# STM32MP25XXAK_Power.net
KiCad netlist of a schematic drawn in Altium Designer
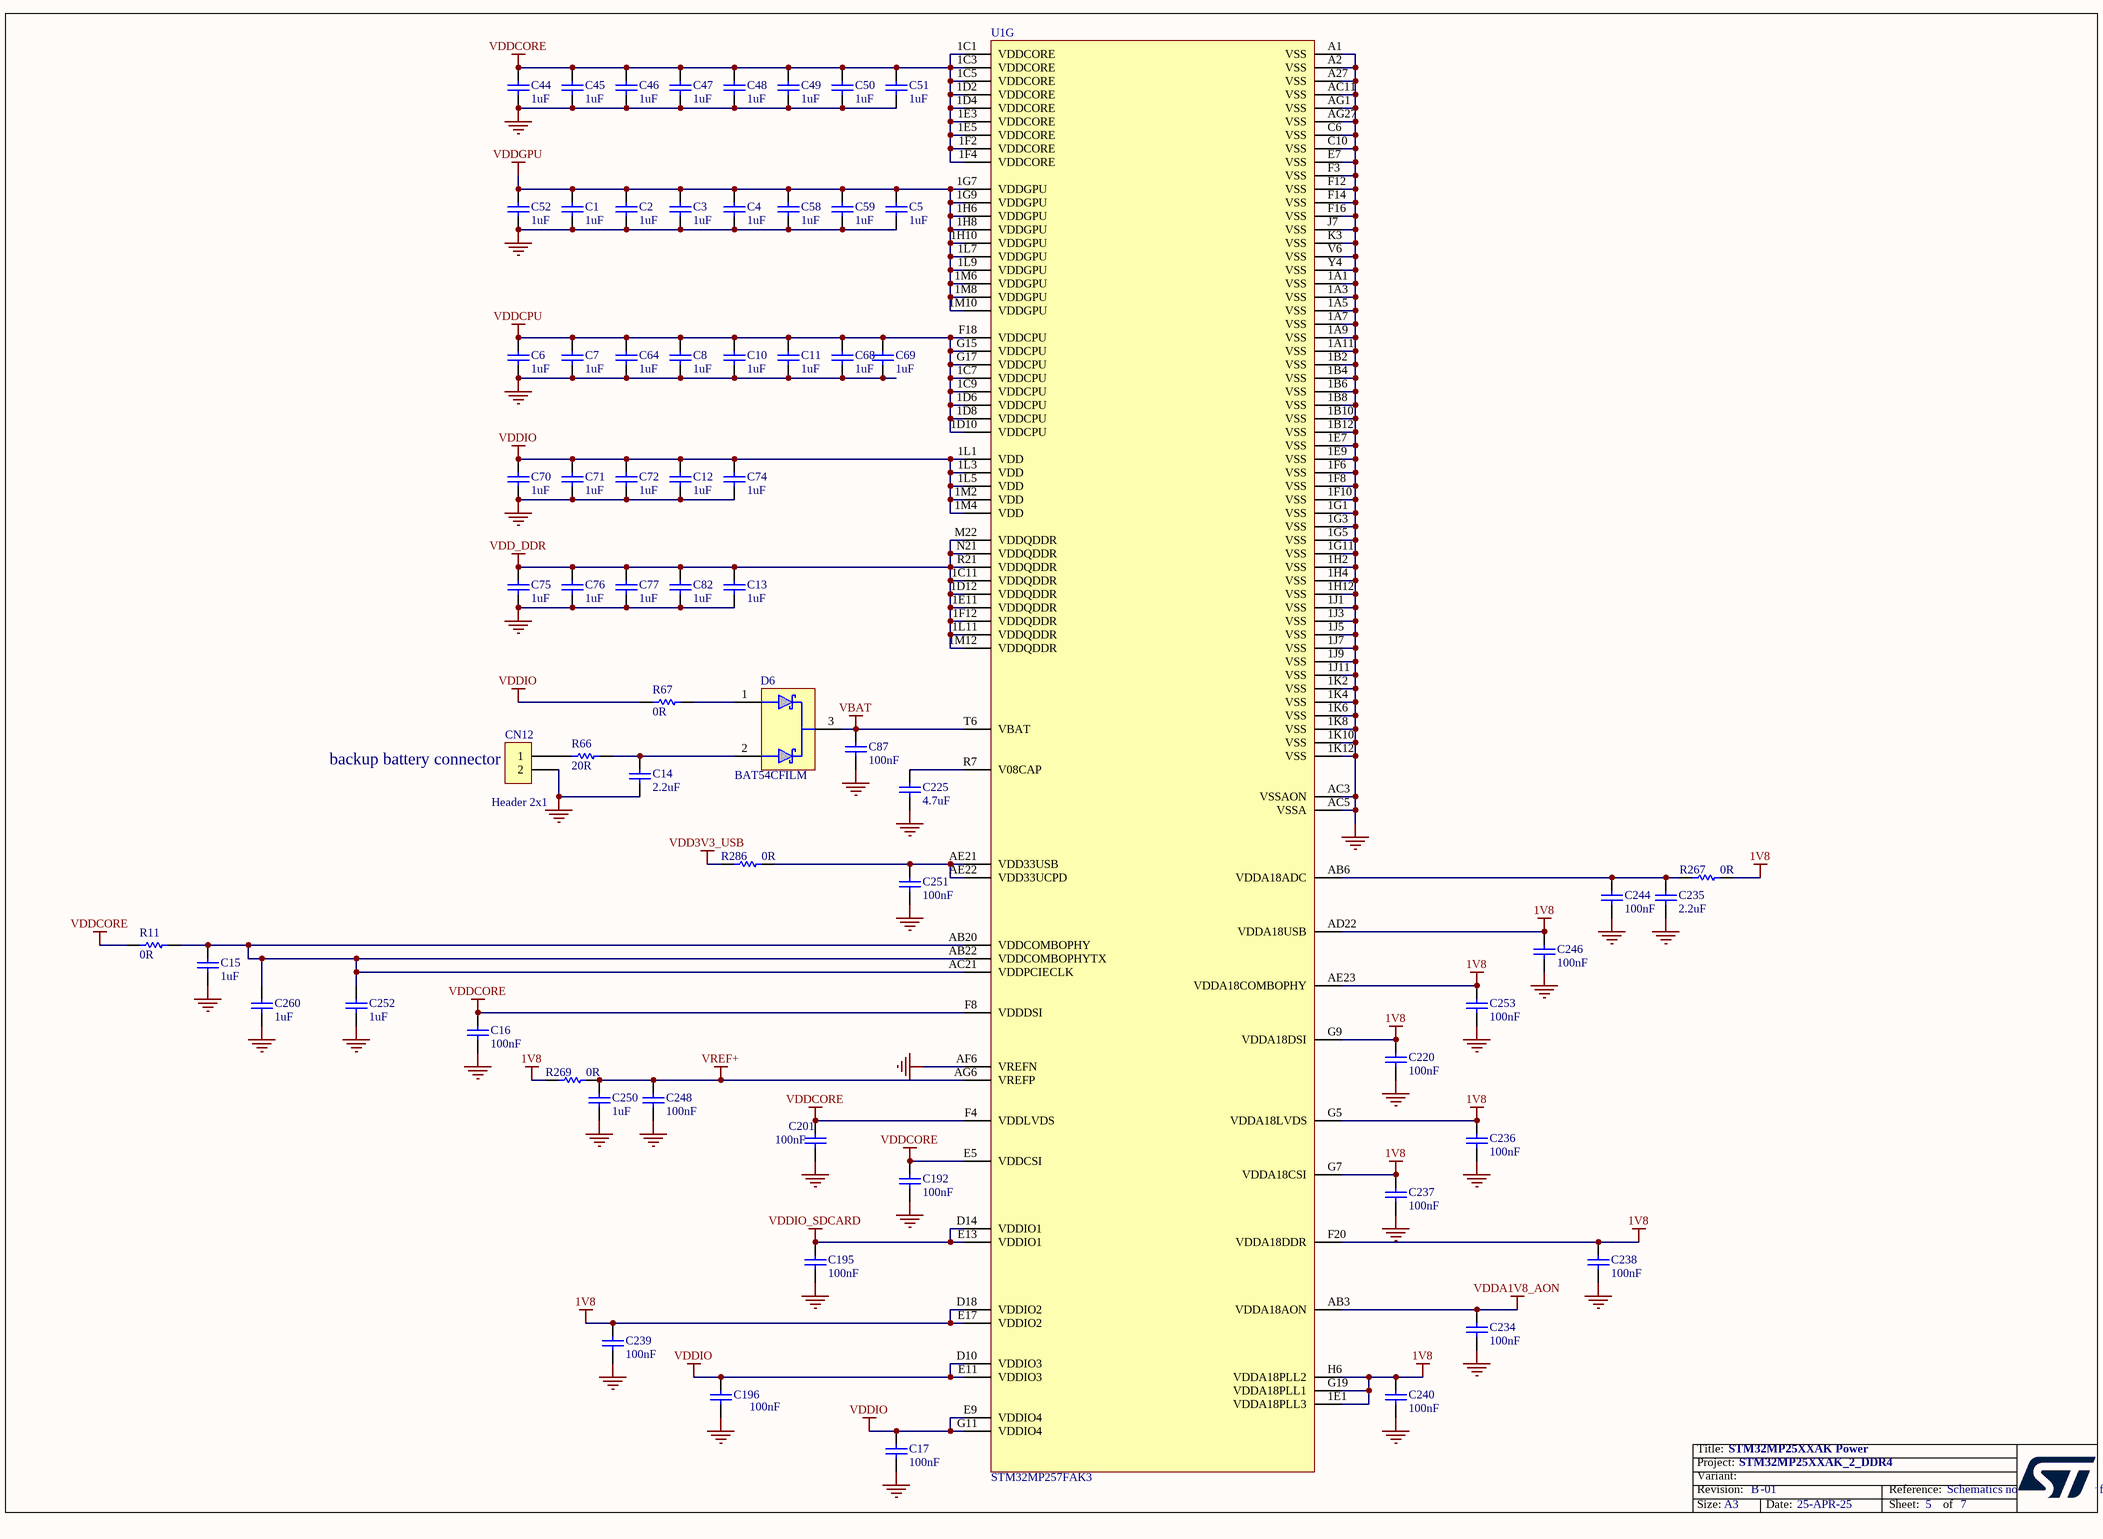
[diagram p0: STM32MP25XXAK Power.SchDoc]

(export (version "E")
  (design (tool "Eeschema 10.0.6"))
  (components
    (comp (ref "C1")
      (value "1uF")
      (footprint "C0201_MURATA_GRM033_H0P3")
      (description "Capacitor, MLCC, 1uF, 6.3V, X5R, +/-20%, 0201, T=0,3mm")
      (fields (field (name "INTERNAL_PART_NUMBER") "MCD-02377") (field (name "MANUFACTURER") "MURATA"))
      (libsource (lib "MCD_PARTS_database") (part "Capacitor"))
    )
    (comp (ref "C2")
      (value "1uF")
      (footprint "C0201_MURATA_GRM033_H0P3")
      (description "Capacitor, MLCC, 1uF, 6.3V, X5R, +/-20%, 0201, T=0,3mm")
      (fields (field (name "INTERNAL_PART_NUMBER") "MCD-02377") (field (name "MANUFACTURER") "MURATA"))
      (libsource (lib "MCD_PARTS_database") (part "Capacitor"))
    )
    (comp (ref "C3")
      (value "1uF")
      (footprint "C0201_MURATA_GRM033_H0P3")
      (description "Capacitor, MLCC, 1uF, 6.3V, X5R, +/-20%, 0201, T=0,3mm")
      (fields (field (name "INTERNAL_PART_NUMBER") "MCD-02377") (field (name "MANUFACTURER") "MURATA"))
      (libsource (lib "MCD_PARTS_database") (part "Capacitor"))
    )
    (comp (ref "C4")
      (value "1uF")
      (footprint "C0201_MURATA_GRM033_H0P3")
      (description "Capacitor, MLCC, 1uF, 6.3V, X5R, +/-20%, 0201, T=0,3mm")
      (fields (field (name "INTERNAL_PART_NUMBER") "MCD-02377") (field (name "MANUFACTURER") "MURATA"))
      (libsource (lib "MCD_PARTS_database") (part "Capacitor"))
    )
    (comp (ref "C5")
      (value "1uF")
      (footprint "C0201_MURATA_GRM033_H0P3")
      (description "Capacitor, MLCC, 1uF, 6.3V, X5R, +/-20%, 0201, T=0,3mm")
      (fields (field (name "INTERNAL_PART_NUMBER") "MCD-02377") (field (name "MANUFACTURER") "MURATA"))
      (libsource (lib "MCD_PARTS_database") (part "Capacitor"))
    )
    (comp (ref "C6")
      (value "1uF")
      (footprint "C0201_MURATA_GRM033_H0P3")
      (description "Capacitor, MLCC, 1uF, 6.3V, X5R, +/-20%, 0201, T=0,3mm")
      (fields (field (name "INTERNAL_PART_NUMBER") "MCD-02377") (field (name "MANUFACTURER") "MURATA"))
      (libsource (lib "MCD_PARTS_database") (part "Capacitor"))
    )
    (comp (ref "C7")
      (value "1uF")
      (footprint "C0201_MURATA_GRM033_H0P3")
      (description "Capacitor, MLCC, 1uF, 6.3V, X5R, +/-20%, 0201, T=0,3mm")
      (fields (field (name "INTERNAL_PART_NUMBER") "MCD-02377") (field (name "MANUFACTURER") "MURATA"))
      (libsource (lib "MCD_PARTS_database") (part "Capacitor"))
    )
    (comp (ref "C8")
      (value "1uF")
      (footprint "C0201_MURATA_GRM033_H0P3")
      (description "Capacitor, MLCC, 1uF, 6.3V, X5R, +/-20%, 0201, T=0,3mm")
      (fields (field (name "INTERNAL_PART_NUMBER") "MCD-02377") (field (name "MANUFACTURER") "MURATA"))
      (libsource (lib "MCD_PARTS_database") (part "Capacitor"))
    )
    (comp (ref "C10")
      (value "1uF")
      (footprint "C0201_MURATA_GRM033_H0P3")
      (description "Capacitor, MLCC, 1uF, 6.3V, X5R, +/-20%, 0201, T=0,3mm")
      (fields (field (name "INTERNAL_PART_NUMBER") "MCD-02377") (field (name "MANUFACTURER") "MURATA"))
      (libsource (lib "MCD_PARTS_database") (part "Capacitor"))
    )
    (comp (ref "C11")
      (value "1uF")
      (footprint "C0201_MURATA_GRM033_H0P3")
      (description "Capacitor, MLCC, 1uF, 6.3V, X5R, +/-20%, 0201, T=0,3mm")
      (fields (field (name "INTERNAL_PART_NUMBER") "MCD-02377") (field (name "MANUFACTURER") "MURATA"))
      (libsource (lib "MCD_PARTS_database") (part "Capacitor"))
    )
    (comp (ref "C12")
      (value "1uF")
      (footprint "C0201_MURATA_GRM033_H0P3")
      (description "Capacitor, MLCC, 1uF, 6.3V, X5R, +/-20%, 0201, T=0,3mm")
      (fields (field (name "INTERNAL_PART_NUMBER") "MCD-02377") (field (name "MANUFACTURER") "MURATA"))
      (libsource (lib "MCD_PARTS_database") (part "Capacitor"))
    )
    (comp (ref "C13")
      (value "1uF")
      (footprint "C0201_MURATA_GRM033_H0P3")
      (description "Capacitor, MLCC, 1uF, 6.3V, X5R, +/-20%, 0201, T=0,3mm")
      (fields (field (name "INTERNAL_PART_NUMBER") "MCD-02377") (field (name "MANUFACTURER") "MURATA"))
      (libsource (lib "MCD_PARTS_database") (part "Capacitor"))
    )
    (comp (ref "C14")
      (value "2.2uF")
      (footprint "C0402")
      (description "Capacitor, MLCC, 2.2uF, 6V3, X5R,+/-10%, 0402, T=0.5mm")
      (fields (field (name "INTERNAL_PART_NUMBER") "MCD-01823") (field (name "MANUFACTURER") "MURATA"))
      (libsource (lib "MCD_PARTS_database") (part "Capacitor"))
    )
    (comp (ref "C15")
      (value "1uF")
      (footprint "C0201_MURATA_GRM033_H0P3")
      (description "Capacitor, MLCC, 1uF, 6.3V, X5R, +/-20%, 0201, T=0,3mm")
      (fields
        (field (name "INTERNAL_PART_NUMBER") "MCD-02377")
        (field (name "MANUFACTURER_PART_NUMBER") "GRM033R60J105MEA2")
      )
      (libsource (lib "MCD_PARTS_database") (part "Capacitor"))
    )
    (comp (ref "C16")
      (value "100nF")
      (footprint "C0201_MURATA_GRM033_H0P3")
      (description "Capacitor, MLCC,100nF, 10V, X7R, +/-10%, 0201, T=0.3mm")
      (fields (field (name "INTERNAL_PART_NUMBER") "MCD-01535") (field (name "MANUFACTURER") "MURATA"))
      (libsource (lib "MCD_PARTS_database") (part "Capacitor"))
    )
    (comp (ref "C17")
      (value "100nF")
      (footprint "C0201_MURATA_GRM033_H0P3")
      (description "Capacitor, MLCC,100nF, 10V, X7R, +/-10%, 0201, T=0.3mm")
      (fields (field (name "INTERNAL_PART_NUMBER") "MCD-01535") (field (name "MANUFACTURER") "MURATA"))
      (libsource (lib "MCD_PARTS_database") (part "Capacitor"))
    )
    (comp (ref "C44")
      (value "1uF")
      (footprint "C0201_MURATA_GRM033_H0P3")
      (description "Capacitor, MLCC, 1uF, 6.3V, X5R, +/-20%, 0201, T=0,3mm")
      (fields (field (name "INTERNAL_PART_NUMBER") "MCD-02377") (field (name "MANUFACTURER") "MURATA"))
      (libsource (lib "MCD_PARTS_database") (part "Capacitor"))
    )
    (comp (ref "C45")
      (value "1uF")
      (footprint "C0201_MURATA_GRM033_H0P3")
      (description "Capacitor, MLCC, 1uF, 6.3V, X5R, +/-20%, 0201, T=0,3mm")
      (fields (field (name "INTERNAL_PART_NUMBER") "MCD-02377") (field (name "MANUFACTURER") "MURATA"))
      (libsource (lib "MCD_PARTS_database") (part "Capacitor"))
    )
    (comp (ref "C46")
      (value "1uF")
      (footprint "C0201_MURATA_GRM033_H0P3")
      (description "Capacitor, MLCC, 1uF, 6.3V, X5R, +/-20%, 0201, T=0,3mm")
      (fields (field (name "INTERNAL_PART_NUMBER") "MCD-02377") (field (name "MANUFACTURER") "MURATA"))
      (libsource (lib "MCD_PARTS_database") (part "Capacitor"))
    )
    (comp (ref "C47")
      (value "1uF")
      (footprint "C0201_MURATA_GRM033_H0P3")
      (description "Capacitor, MLCC, 1uF, 6.3V, X5R, +/-20%, 0201, T=0,3mm")
      (fields (field (name "INTERNAL_PART_NUMBER") "MCD-02377") (field (name "MANUFACTURER") "MURATA"))
      (libsource (lib "MCD_PARTS_database") (part "Capacitor"))
    )
    (comp (ref "C48")
      (value "1uF")
      (footprint "C0201_MURATA_GRM033_H0P3")
      (description "Capacitor, MLCC, 1uF, 6.3V, X5R, +/-20%, 0201, T=0,3mm")
      (fields (field (name "INTERNAL_PART_NUMBER") "MCD-02377") (field (name "MANUFACTURER") "MURATA"))
      (libsource (lib "MCD_PARTS_database") (part "Capacitor"))
    )
    (comp (ref "C49")
      (value "1uF")
      (footprint "C0201_MURATA_GRM033_H0P3")
      (description "Capacitor, MLCC, 1uF, 6.3V, X5R, +/-20%, 0201, T=0,3mm")
      (fields (field (name "INTERNAL_PART_NUMBER") "MCD-02377") (field (name "MANUFACTURER") "MURATA"))
      (libsource (lib "MCD_PARTS_database") (part "Capacitor"))
    )
    (comp (ref "C50")
      (value "1uF")
      (footprint "C0201_MURATA_GRM033_H0P3")
      (description "Capacitor, MLCC, 1uF, 6.3V, X5R, +/-20%, 0201, T=0,3mm")
      (fields (field (name "INTERNAL_PART_NUMBER") "MCD-02377") (field (name "MANUFACTURER") "MURATA"))
      (libsource (lib "MCD_PARTS_database") (part "Capacitor"))
    )
    (comp (ref "C51")
      (value "1uF")
      (footprint "C0201_MURATA_GRM033_H0P3")
      (description "Capacitor, MLCC, 1uF, 6.3V, X5R, +/-20%, 0201, T=0,3mm")
      (fields (field (name "INTERNAL_PART_NUMBER") "MCD-02377") (field (name "MANUFACTURER") "MURATA"))
      (libsource (lib "MCD_PARTS_database") (part "Capacitor"))
    )
    (comp (ref "C52")
      (value "1uF")
      (footprint "C0201_MURATA_GRM033_H0P3")
      (description "Capacitor, MLCC, 1uF, 6.3V, X5R, +/-20%, 0201, T=0,3mm")
      (fields (field (name "INTERNAL_PART_NUMBER") "MCD-02377") (field (name "MANUFACTURER") "MURATA"))
      (libsource (lib "MCD_PARTS_database") (part "Capacitor"))
    )
    (comp (ref "C58")
      (value "1uF")
      (footprint "C0201_MURATA_GRM033_H0P3")
      (description "Capacitor, MLCC, 1uF, 6.3V, X5R, +/-20%, 0201, T=0,3mm")
      (fields (field (name "INTERNAL_PART_NUMBER") "MCD-02377") (field (name "MANUFACTURER") "MURATA"))
      (libsource (lib "MCD_PARTS_database") (part "Capacitor"))
    )
    (comp (ref "C59")
      (value "1uF")
      (footprint "C0201_MURATA_GRM033_H0P3")
      (description "Capacitor, MLCC, 1uF, 6.3V, X5R, +/-20%, 0201, T=0,3mm")
      (fields (field (name "INTERNAL_PART_NUMBER") "MCD-02377") (field (name "MANUFACTURER") "MURATA"))
      (libsource (lib "MCD_PARTS_database") (part "Capacitor"))
    )
    (comp (ref "C64")
      (value "1uF")
      (footprint "C0201_MURATA_GRM033_H0P3")
      (description "Capacitor, MLCC, 1uF, 6.3V, X5R, +/-20%, 0201, T=0,3mm")
      (fields (field (name "INTERNAL_PART_NUMBER") "MCD-02377") (field (name "MANUFACTURER") "MURATA"))
      (libsource (lib "MCD_PARTS_database") (part "Capacitor"))
    )
    (comp (ref "C68")
      (value "1uF")
      (footprint "C0201_MURATA_GRM033_H0P3")
      (description "Capacitor, MLCC, 1uF, 6.3V, X5R, +/-20%, 0201, T=0,3mm")
      (fields (field (name "INTERNAL_PART_NUMBER") "MCD-02377") (field (name "MANUFACTURER") "MURATA"))
      (libsource (lib "MCD_PARTS_database") (part "Capacitor"))
    )
    (comp (ref "C69")
      (value "1uF")
      (footprint "C0201_MURATA_GRM033_H0P3")
      (description "Capacitor, MLCC, 1uF, 6.3V, X5R, +/-20%, 0201, T=0,3mm")
      (fields (field (name "INTERNAL_PART_NUMBER") "MCD-02377") (field (name "MANUFACTURER") "MURATA"))
      (libsource (lib "MCD_PARTS_database") (part "Capacitor"))
    )
    (comp (ref "C70")
      (value "1uF")
      (footprint "C0201_MURATA_GRM033_H0P3")
      (description "Capacitor, MLCC, 1uF, 6.3V, X5R, +/-20%, 0201, T=0,3mm")
      (fields (field (name "INTERNAL_PART_NUMBER") "MCD-02377") (field (name "MANUFACTURER") "MURATA"))
      (libsource (lib "MCD_PARTS_database") (part "Capacitor"))
    )
    (comp (ref "C71")
      (value "1uF")
      (footprint "C0201_MURATA_GRM033_H0P3")
      (description "Capacitor, MLCC, 1uF, 6.3V, X5R, +/-20%, 0201, T=0,3mm")
      (fields (field (name "INTERNAL_PART_NUMBER") "MCD-02377") (field (name "MANUFACTURER") "MURATA"))
      (libsource (lib "MCD_PARTS_database") (part "Capacitor"))
    )
    (comp (ref "C72")
      (value "1uF")
      (footprint "C0201_MURATA_GRM033_H0P3")
      (description "Capacitor, MLCC, 1uF, 6.3V, X5R, +/-20%, 0201, T=0,3mm")
      (fields (field (name "INTERNAL_PART_NUMBER") "MCD-02377") (field (name "MANUFACTURER") "MURATA"))
      (libsource (lib "MCD_PARTS_database") (part "Capacitor"))
    )
    (comp (ref "C74")
      (value "1uF")
      (footprint "C0201_MURATA_GRM033_H0P3")
      (description "Capacitor, MLCC, 1uF, 6.3V, X5R, +/-20%, 0201, T=0,3mm")
      (fields (field (name "INTERNAL_PART_NUMBER") "MCD-02377") (field (name "MANUFACTURER") "MURATA"))
      (libsource (lib "MCD_PARTS_database") (part "Capacitor"))
    )
    (comp (ref "C75")
      (value "1uF")
      (footprint "C0201_MURATA_GRM033_H0P3")
      (description "Capacitor, MLCC, 1uF, 6.3V, X5R, +/-20%, 0201, T=0,3mm")
      (fields (field (name "INTERNAL_PART_NUMBER") "MCD-02377") (field (name "MANUFACTURER") "MURATA"))
      (libsource (lib "MCD_PARTS_database") (part "Capacitor"))
    )
    (comp (ref "C76")
      (value "1uF")
      (footprint "C0201_MURATA_GRM033_H0P3")
      (description "Capacitor, MLCC, 1uF, 6.3V, X5R, +/-20%, 0201, T=0,3mm")
      (fields (field (name "INTERNAL_PART_NUMBER") "MCD-02377") (field (name "MANUFACTURER") "MURATA"))
      (libsource (lib "MCD_PARTS_database") (part "Capacitor"))
    )
    (comp (ref "C77")
      (value "1uF")
      (footprint "C0201_MURATA_GRM033_H0P3")
      (description "Capacitor, MLCC, 1uF, 6.3V, X5R, +/-20%, 0201, T=0,3mm")
      (fields (field (name "INTERNAL_PART_NUMBER") "MCD-02377") (field (name "MANUFACTURER") "MURATA"))
      (libsource (lib "MCD_PARTS_database") (part "Capacitor"))
    )
    (comp (ref "C82")
      (value "1uF")
      (footprint "C0201_MURATA_GRM033_H0P3")
      (description "Capacitor, MLCC, 1uF, 6.3V, X5R, +/-20%, 0201, T=0,3mm")
      (fields (field (name "INTERNAL_PART_NUMBER") "MCD-02377") (field (name "MANUFACTURER") "MURATA"))
      (libsource (lib "MCD_PARTS_database") (part "Capacitor"))
    )
    (comp (ref "C87")
      (value "100nF")
      (footprint "C0402")
      (description "Capacitor,100nF,16V,X7R,10%,0402")
      (fields
        (field (name "INTERNAL_PART_NUMBER") "MCD-00006")
        (field (name "MANUFACTURER_PART_NUMBER") "CC0402KRX7R7BB104")
        (field (name "PROVIDED_BY") "SUBCO")
      )
      (libsource (lib "MCD_PARTS_database") (part "Capacitor"))
    )
    (comp (ref "C192")
      (value "100nF")
      (footprint "C0201_MURATA_GRM033_H0P3")
      (description "Capacitor, MLCC,100nF, 10V, X7R, +/-10%, 0201, T=0.3mm")
      (fields (field (name "INTERNAL_PART_NUMBER") "MCD-01535") (field (name "MANUFACTURER") "MURATA"))
      (libsource (lib "MCD_PARTS_database") (part "Capacitor"))
    )
    (comp (ref "C195")
      (value "100nF")
      (footprint "C0201_MURATA_GRM033_H0P3")
      (description "Capacitor, MLCC,100nF, 10V, X7R, +/-10%, 0201, T=0.3mm")
      (fields (field (name "INTERNAL_PART_NUMBER") "MCD-01535") (field (name "MANUFACTURER") "MURATA"))
      (libsource (lib "MCD_PARTS_database") (part "Capacitor"))
    )
    (comp (ref "C196")
      (value "100nF")
      (footprint "C0201_MURATA_GRM033_H0P3")
      (description "Capacitor, MLCC,100nF, 10V, X7R, +/-10%, 0201, T=0.3mm")
      (fields (field (name "INTERNAL_PART_NUMBER") "MCD-01535") (field (name "MANUFACTURER") "MURATA"))
      (libsource (lib "MCD_PARTS_database") (part "Capacitor"))
    )
    (comp (ref "C201")
      (value "100nF")
      (footprint "C0201_MURATA_GRM033_H0P3")
      (description "Capacitor, MLCC,100nF, 10V, X7R, +/-10%, 0201, T=0.3mm")
      (fields (field (name "INTERNAL_PART_NUMBER") "MCD-01535") (field (name "MANUFACTURER") "MURATA"))
      (libsource (lib "MCD_PARTS_database") (part "Capacitor"))
    )
    (comp (ref "C220")
      (value "100nF")
      (footprint "C0201_MURATA_GRM033_H0P3")
      (description "Capacitor, MLCC,100nF, 10V, X7R, +/-10%, 0201, T=0.3mm")
      (fields (field (name "INTERNAL_PART_NUMBER") "MCD-01535") (field (name "MANUFACTURER") "MURATA"))
      (libsource (lib "MCD_PARTS_database") (part "Capacitor"))
    )
    (comp (ref "C225")
      (value "4.7uF")
      (footprint "C0201_H0P5")
      (description "Capacitor, MLCC, 4,7uF, 6V3, X5R, +/-20%, 0201, T=0.5mm")
      (fields (field (name "INTERNAL_PART_NUMBER") "MCD-01534") (field (name "MANUFACTURER") "MURATA"))
      (libsource (lib "MCD_PARTS_database") (part "Capacitor"))
    )
    (comp (ref "C234")
      (value "100nF")
      (footprint "C0201_MURATA_GRM033_H0P3")
      (description "Capacitor, MLCC,100nF, 10V, X7R, +/-10%, 0201, T=0.3mm")
      (fields (field (name "INTERNAL_PART_NUMBER") "MCD-01535") (field (name "MANUFACTURER") "MURATA"))
      (libsource (lib "MCD_PARTS_database") (part "Capacitor"))
    )
    (comp (ref "C235")
      (value "2.2uF")
      (footprint "C0201_H0P5")
      (description "Capacitor, MLCC, 2.2uF, 10V, X5R,+/-10%, 0201, T=0.5mm")
      (fields (field (name "INTERNAL_PART_NUMBER") "MCD-02235") (field (name "MANUFACTURER") "MURATA"))
      (libsource (lib "MCD_PARTS_database") (part "Capacitor"))
    )
    (comp (ref "C236")
      (value "100nF")
      (footprint "C0201_MURATA_GRM033_H0P3")
      (description "Capacitor, MLCC,100nF, 10V, X7R, +/-10%, 0201, T=0.3mm")
      (fields (field (name "INTERNAL_PART_NUMBER") "MCD-01535") (field (name "MANUFACTURER") "MURATA"))
      (libsource (lib "MCD_PARTS_database") (part "Capacitor"))
    )
    (comp (ref "C237")
      (value "100nF")
      (footprint "C0201_MURATA_GRM033_H0P3")
      (description "Capacitor, MLCC,100nF, 10V, X7R, +/-10%, 0201, T=0.3mm")
      (fields (field (name "INTERNAL_PART_NUMBER") "MCD-01535") (field (name "MANUFACTURER") "MURATA"))
      (libsource (lib "MCD_PARTS_database") (part "Capacitor"))
    )
    (comp (ref "C238")
      (value "100nF")
      (footprint "C0201_MURATA_GRM033_H0P3")
      (description "Capacitor, MLCC,100nF, 10V, X7R, +/-10%, 0201, T=0.3mm")
      (fields (field (name "INTERNAL_PART_NUMBER") "MCD-01535") (field (name "MANUFACTURER") "MURATA"))
      (libsource (lib "MCD_PARTS_database") (part "Capacitor"))
    )
    (comp (ref "C239")
      (value "100nF")
      (footprint "C0201_MURATA_GRM033_H0P3")
      (description "Capacitor, MLCC,100nF, 10V, X7R, +/-10%, 0201, T=0.3mm")
      (fields (field (name "INTERNAL_PART_NUMBER") "MCD-01535") (field (name "MANUFACTURER") "MURATA"))
      (libsource (lib "MCD_PARTS_database") (part "Capacitor"))
    )
    (comp (ref "C240")
      (value "100nF")
      (footprint "C0201_MURATA_GRM033_H0P3")
      (description "Capacitor, MLCC,100nF, 10V, X7R, +/-10%, 0201, T=0.3mm")
      (fields (field (name "INTERNAL_PART_NUMBER") "MCD-01535") (field (name "MANUFACTURER") "MURATA"))
      (libsource (lib "MCD_PARTS_database") (part "Capacitor"))
    )
    (comp (ref "C244")
      (value "100nF")
      (footprint "C0201_MURATA_GRM033_H0P3")
      (description "Capacitor, MLCC,100nF, 10V, X7R, +/-10%, 0201, T=0.3mm")
      (fields (field (name "INTERNAL_PART_NUMBER") "MCD-01535") (field (name "MANUFACTURER") "MURATA"))
      (libsource (lib "MCD_PARTS_database") (part "Capacitor"))
    )
    (comp (ref "C246")
      (value "100nF")
      (footprint "C0201_MURATA_GRM033_H0P3")
      (description "Capacitor, MLCC,100nF, 10V, X7R, +/-10%, 0201, T=0.3mm")
      (fields (field (name "INTERNAL_PART_NUMBER") "MCD-01535") (field (name "MANUFACTURER") "MURATA"))
      (libsource (lib "MCD_PARTS_database") (part "Capacitor"))
    )
    (comp (ref "C248")
      (value "100nF")
      (footprint "C0201_MURATA_GRM033_H0P3")
      (description "Capacitor, MLCC,100nF, 10V, X7R, +/-10%, 0201, T=0.3mm")
      (fields (field (name "INTERNAL_PART_NUMBER") "MCD-01535") (field (name "MANUFACTURER") "MURATA"))
      (libsource (lib "MCD_PARTS_database") (part "Capacitor"))
    )
    (comp (ref "C250")
      (value "1uF")
      (footprint "C0201_MURATA_GRM033_H0P3")
      (description "Capacitor, MLCC, 1uF, 6.3V, X5R, +/-20%, 0201, T=0,3mm")
      (fields
        (field (name "INTERNAL_PART_NUMBER") "MCD-02377")
        (field (name "MANUFACTURER_PART_NUMBER") "GRM033R60J105MEA2")
      )
      (libsource (lib "MCD_PARTS_database") (part "Capacitor"))
    )
    (comp (ref "C251")
      (value "100nF")
      (footprint "C0201_MURATA_GRM033_H0P3")
      (description "Capacitor, MLCC,100nF, 10V, X7R, +/-10%, 0201, T=0.3mm")
      (fields (field (name "INTERNAL_PART_NUMBER") "MCD-01535") (field (name "MANUFACTURER") "MURATA"))
      (libsource (lib "MCD_PARTS_database") (part "Capacitor"))
    )
    (comp (ref "C252")
      (value "1uF")
      (footprint "C0201_MURATA_GRM033_H0P3")
      (description "Capacitor, MLCC, 1uF, 6.3V, X5R, +/-20%, 0201, T=0,3mm")
      (fields
        (field (name "INTERNAL_PART_NUMBER") "MCD-02377")
        (field (name "MANUFACTURER_PART_NUMBER") "GRM033R60J105MEA2")
      )
      (libsource (lib "MCD_PARTS_database") (part "Capacitor"))
    )
    (comp (ref "C253")
      (value "100nF")
      (footprint "C0201_MURATA_GRM033_H0P3")
      (description "Capacitor, MLCC,100nF, 10V, X7R, +/-10%, 0201, T=0.3mm")
      (fields (field (name "INTERNAL_PART_NUMBER") "MCD-01535") (field (name "MANUFACTURER") "MURATA"))
      (libsource (lib "MCD_PARTS_database") (part "Capacitor"))
    )
    (comp (ref "C260")
      (value "1uF")
      (footprint "C0201_MURATA_GRM033_H0P3")
      (description "Capacitor, MLCC, 1uF, 6.3V, X5R, +/-20%, 0201, T=0,3mm")
      (fields
        (field (name "INTERNAL_PART_NUMBER") "MCD-02377")
        (field (name "MANUFACTURER_PART_NUMBER") "GRM033R60J105MEA2")
      )
      (libsource (lib "MCD_PARTS_database") (part "Capacitor"))
    )
    (comp (ref "CN12")
      (value "Header 2x1")
      (footprint "CON_MOLEX_53047-0210")
      (description "Header 2 circuits, 1.25mm Pitch ,  Vertical, with Friction Lock")
      (fields
        (field (name "INTERNAL_PART_NUMBER") "MCD-00655")
        (field (name "MANUFACTURER_PART_NUMBER") "53047-0210")
        (field (name "PROVIDED_BY") "SUBCO")
      )
      (libsource (lib "MCD_PARTS_database") (part "Header 2x1"))
    )
    (comp (ref "D6")
      (value "BAT54CFILM")
      (footprint "DIO_SOT23")
      (description "Diode, Schottky, Dual Common Cathode, 0V3, 300mA, 40V, SOT-23")
      (fields
        (field (name "INTERNAL_PART_NUMBER") "MCD-03280")
        (field (name "MANUFACTURER") "STMICROELECTRONICS")
      )
      (libsource (lib "MCD_PARTS_database") (part "DIODE_3P_DUAL_COMMON_CATHODE"))
    )
    (comp (ref "R11")
      (value "0R")
      (footprint "R0603")
      (description "Resistor, 0R, 0603, +/-5%, 1/10W")
      (fields (field (name "INTERNAL_PART_NUMBER") "MCD-00056") (field (name "MANUFACTURER") "YAGEO"))
      (libsource (lib "MCD_PARTS_database") (part "Resistor"))
    )
    (comp (ref "R66")
      (value "20R")
      (footprint "R0402")
      (description "Resistor, 20R, 0402, +/-1%, 1/16W")
      (fields (field (name "INTERNAL_PART_NUMBER") "MCD-00058") (field (name "BMS_PART_NUMBER") "9131027"))
      (libsource (lib "MCD_PARTS_database") (part "Resistor"))
    )
    (comp (ref "R67")
      (value "0R")
      (footprint "R0402")
      (description "Resistor, 0R, 0402, +/-5%, 1/16W")
      (fields
        (field (name "INTERNAL_PART_NUMBER") "MCD-00052")
        (field (name "MANUFACTURER_PART_NUMBER") "RC0402JR-070RL")
      )
      (libsource (lib "MCD_PARTS_database") (part "Resistor"))
    )
    (comp (ref "R267")
      (value "0R")
      (footprint "R0402")
      (description "Resistor,0R,0402,5%,1/16W")
      (fields
        (field (name "INTERNAL_PART_NUMBER") "MCD-00052")
        (field (name "MANUFACTURER_PART_NUMBER") "RC0402JR-070RL")
        (field (name "PROVIDED_BY") "SUBCO")
      )
      (libsource (lib "MCD_PARTS_database") (part "Resistor"))
    )
    (comp (ref "R269")
      (value "0R")
      (footprint "R0402")
      (description "Resistor,0R,0402,5%,1/16W")
      (fields
        (field (name "INTERNAL_PART_NUMBER") "MCD-00052")
        (field (name "MANUFACTURER_PART_NUMBER") "RC0402JR-070RL")
        (field (name "PROVIDED_BY") "SUBCO")
      )
      (libsource (lib "MCD_PARTS_database") (part "Resistor"))
    )
    (comp (ref "R286")
      (value "0R")
      (footprint "R0402")
      (description "Resistor,0R,0402,5%,1/16W")
      (fields
        (field (name "INTERNAL_PART_NUMBER") "MCD-00052")
        (field (name "MANUFACTURER_PART_NUMBER") "RC0402JR-070RL")
        (field (name "PROVIDED_BY") "SUBCO")
      )
      (libsource (lib "MCD_PARTS_database") (part "Resistor"))
    )
    (comp (ref "U1")
      (value "STM32MP257FAK3")
      (footprint "ICC_TFBGA424_14X14_P050_H1P20_CODE-B0A2")
      (description "MPU , 2xCortex-A35@1.5GHz, Cortex-M33@400MHz, TFBGA 14x14, pitch 0.5, 648KB SRAM, With Crypto")
      (fields
        (field (name "INTERNAL_PART_NUMBER") "MCD-03375")
        (field (name "MANUFACTURER") "STMICROELECTRONICS")
      )
      (libsource (lib "MCD_PARTS_database") (part "STM32MP257FAK3"))
    )
  )
  (nets
    (net (code "1") (name "1V8") (class "Default")
      (node (ref "C220") (pin "2") (pinfunction "2_2") (pintype "passive"))
      (node (ref "C236") (pin "2") (pinfunction "2_2") (pintype "passive"))
      (node (ref "C237") (pin "2") (pinfunction "2_2") (pintype "passive"))
      (node (ref "C238") (pin "2") (pinfunction "2_2") (pintype "passive"))
      (node (ref "C239") (pin "2") (pinfunction "2_2") (pintype "passive"))
      (node (ref "C240") (pin "2") (pinfunction "2_2") (pintype "passive"))
      (node (ref "C246") (pin "2") (pinfunction "2_2") (pintype "passive"))
      (node (ref "C253") (pin "2") (pinfunction "2_2") (pintype "passive"))
      (node (ref "R267") (pin "2") (pinfunction "2_2") (pintype "passive"))
      (node (ref "R269") (pin "1") (pinfunction "1_1") (pintype "passive"))
      (node (ref "U1") (pin "1E1") (pinfunction "VDDA18PLL3_1E1") (pintype "passive"))
      (node (ref "U1") (pin "AD22") (pinfunction "VDDA18USB_AD22") (pintype "passive"))
      (node (ref "U1") (pin "AE23") (pinfunction "VDDA18COMBOPHY_AE23") (pintype "passive"))
      (node (ref "U1") (pin "D18") (pinfunction "VDDIO2_D18") (pintype "passive"))
      (node (ref "U1") (pin "E17") (pinfunction "VDDIO2_E17") (pintype "passive"))
      (node (ref "U1") (pin "F20") (pinfunction "VDDA18DDR_F20") (pintype "passive"))
      (node (ref "U1") (pin "G19") (pinfunction "VDDA18PLL1_G19") (pintype "passive"))
      (node (ref "U1") (pin "G5") (pinfunction "VDDA18LVDS_G5") (pintype "passive"))
      (node (ref "U1") (pin "G7") (pinfunction "VDDA18CSI_G7") (pintype "passive"))
      (node (ref "U1") (pin "G9") (pinfunction "VDDA18DSI_G9") (pintype "passive"))
      (node (ref "U1") (pin "H6") (pinfunction "VDDA18PLL2_H6") (pintype "passive"))
    )
    (net (code "2") (name "GND") (class "Default")
      (node (ref "C1") (pin "1") (pinfunction "1_1") (pintype "passive"))
      (node (ref "C10") (pin "1") (pinfunction "1_1") (pintype "passive"))
      (node (ref "C11") (pin "1") (pinfunction "1_1") (pintype "passive"))
      (node (ref "C12") (pin "2") (pinfunction "2_2") (pintype "passive"))
      (node (ref "C13") (pin "1") (pinfunction "1_1") (pintype "passive"))
      (node (ref "C14") (pin "1") (pinfunction "1_1") (pintype "passive"))
      (node (ref "C15") (pin "1") (pinfunction "1_1") (pintype "passive"))
      (node (ref "C16") (pin "1") (pinfunction "1_1") (pintype "passive"))
      (node (ref "C17") (pin "1") (pinfunction "1_1") (pintype "passive"))
      (node (ref "C192") (pin "1") (pinfunction "1_1") (pintype "passive"))
      (node (ref "C195") (pin "1") (pinfunction "1_1") (pintype "passive"))
      (node (ref "C196") (pin "1") (pinfunction "1_1") (pintype "passive"))
      (node (ref "C2") (pin "1") (pinfunction "1_1") (pintype "passive"))
      (node (ref "C201") (pin "1") (pinfunction "1_1") (pintype "passive"))
      (node (ref "C220") (pin "1") (pinfunction "1_1") (pintype "passive"))
      (node (ref "C225") (pin "1") (pinfunction "1_1") (pintype "passive"))
      (node (ref "C234") (pin "1") (pinfunction "1_1") (pintype "passive"))
      (node (ref "C235") (pin "1") (pinfunction "1_1") (pintype "passive"))
      (node (ref "C236") (pin "1") (pinfunction "1_1") (pintype "passive"))
      (node (ref "C237") (pin "1") (pinfunction "1_1") (pintype "passive"))
      (node (ref "C238") (pin "1") (pinfunction "1_1") (pintype "passive"))
      (node (ref "C239") (pin "1") (pinfunction "1_1") (pintype "passive"))
      (node (ref "C240") (pin "1") (pinfunction "1_1") (pintype "passive"))
      (node (ref "C244") (pin "1") (pinfunction "1_1") (pintype "passive"))
      (node (ref "C246") (pin "1") (pinfunction "1_1") (pintype "passive"))
      (node (ref "C248") (pin "1") (pinfunction "1_1") (pintype "passive"))
      (node (ref "C250") (pin "1") (pinfunction "1_1") (pintype "passive"))
      (node (ref "C251") (pin "1") (pinfunction "1_1") (pintype "passive"))
      (node (ref "C252") (pin "1") (pinfunction "1_1") (pintype "passive"))
      (node (ref "C253") (pin "1") (pinfunction "1_1") (pintype "passive"))
      (node (ref "C260") (pin "1") (pinfunction "1_1") (pintype "passive"))
      (node (ref "C3") (pin "1") (pinfunction "1_1") (pintype "passive"))
      (node (ref "C4") (pin "1") (pinfunction "1_1") (pintype "passive"))
      (node (ref "C44") (pin "2") (pinfunction "2_2") (pintype "passive"))
      (node (ref "C45") (pin "1") (pinfunction "1_1") (pintype "passive"))
      (node (ref "C46") (pin "1") (pinfunction "1_1") (pintype "passive"))
      (node (ref "C47") (pin "2") (pinfunction "2_2") (pintype "passive"))
      (node (ref "C48") (pin "1") (pinfunction "1_1") (pintype "passive"))
      (node (ref "C49") (pin "1") (pinfunction "1_1") (pintype "passive"))
      (node (ref "C5") (pin "1") (pinfunction "1_1") (pintype "passive"))
      (node (ref "C50") (pin "1") (pinfunction "1_1") (pintype "passive"))
      (node (ref "C51") (pin "1") (pinfunction "1_1") (pintype "passive"))
      (node (ref "C52") (pin "1") (pinfunction "1_1") (pintype "passive"))
      (node (ref "C58") (pin "1") (pinfunction "1_1") (pintype "passive"))
      (node (ref "C59") (pin "1") (pinfunction "1_1") (pintype "passive"))
      (node (ref "C6") (pin "2") (pinfunction "2_2") (pintype "passive"))
      (node (ref "C64") (pin "1") (pinfunction "1_1") (pintype "passive"))
      (node (ref "C68") (pin "1") (pinfunction "1_1") (pintype "passive"))
      (node (ref "C69") (pin "1") (pinfunction "1_1") (pintype "passive"))
      (node (ref "C7") (pin "1") (pinfunction "1_1") (pintype "passive"))
      (node (ref "C70") (pin "2") (pinfunction "2_2") (pintype "passive"))
      (node (ref "C71") (pin "1") (pinfunction "1_1") (pintype "passive"))
      (node (ref "C72") (pin "1") (pinfunction "1_1") (pintype "passive"))
      (node (ref "C74") (pin "1") (pinfunction "1_1") (pintype "passive"))
      (node (ref "C75") (pin "1") (pinfunction "1_1") (pintype "passive"))
      (node (ref "C76") (pin "1") (pinfunction "1_1") (pintype "passive"))
      (node (ref "C77") (pin "2") (pinfunction "2_2") (pintype "passive"))
      (node (ref "C8") (pin "2") (pinfunction "2_2") (pintype "passive"))
      (node (ref "C82") (pin "1") (pinfunction "1_1") (pintype "passive"))
      (node (ref "C87") (pin "1") (pinfunction "1_1") (pintype "passive"))
      (node (ref "CN12") (pin "2") (pinfunction "2_2") (pintype "passive"))
      (node (ref "U1") (pin "1A1") (pinfunction "VSS_1A1") (pintype "passive"))
      (node (ref "U1") (pin "1A11") (pinfunction "VSS_1A11") (pintype "passive"))
      (node (ref "U1") (pin "1A3") (pinfunction "VSS_1A3") (pintype "passive"))
      (node (ref "U1") (pin "1A5") (pinfunction "VSS_1A5") (pintype "passive"))
      (node (ref "U1") (pin "1A7") (pinfunction "VSS_1A7") (pintype "passive"))
      (node (ref "U1") (pin "1A9") (pinfunction "VSS_1A9") (pintype "passive"))
      (node (ref "U1") (pin "1B10") (pinfunction "VSS_1B10") (pintype "passive"))
      (node (ref "U1") (pin "1B12") (pinfunction "VSS_1B12") (pintype "passive"))
      (node (ref "U1") (pin "1B2") (pinfunction "VSS_1B2") (pintype "passive"))
      (node (ref "U1") (pin "1B4") (pinfunction "VSS_1B4") (pintype "passive"))
      (node (ref "U1") (pin "1B6") (pinfunction "VSS_1B6") (pintype "passive"))
      (node (ref "U1") (pin "1B8") (pinfunction "VSS_1B8") (pintype "passive"))
      (node (ref "U1") (pin "1E7") (pinfunction "VSS_1E7") (pintype "passive"))
      (node (ref "U1") (pin "1E9") (pinfunction "VSS_1E9") (pintype "passive"))
      (node (ref "U1") (pin "1F10") (pinfunction "VSS_1F10") (pintype "passive"))
      (node (ref "U1") (pin "1F6") (pinfunction "VSS_1F6") (pintype "passive"))
      (node (ref "U1") (pin "1F8") (pinfunction "VSS_1F8") (pintype "passive"))
      (node (ref "U1") (pin "1G1") (pinfunction "VSS_1G1") (pintype "passive"))
      (node (ref "U1") (pin "1G11") (pinfunction "VSS_1G11") (pintype "passive"))
      (node (ref "U1") (pin "1G3") (pinfunction "VSS_1G3") (pintype "passive"))
      (node (ref "U1") (pin "1G5") (pinfunction "VSS_1G5") (pintype "passive"))
      (node (ref "U1") (pin "1H12") (pinfunction "VSS_1H12") (pintype "passive"))
      (node (ref "U1") (pin "1H2") (pinfunction "VSS_1H2") (pintype "passive"))
      (node (ref "U1") (pin "1H4") (pinfunction "VSS_1H4") (pintype "passive"))
      (node (ref "U1") (pin "1J1") (pinfunction "VSS_1J1") (pintype "passive"))
      (node (ref "U1") (pin "1J11") (pinfunction "VSS_1J11") (pintype "passive"))
      (node (ref "U1") (pin "1J3") (pinfunction "VSS_1J3") (pintype "passive"))
      (node (ref "U1") (pin "1J5") (pinfunction "VSS_1J5") (pintype "passive"))
      (node (ref "U1") (pin "1J7") (pinfunction "VSS_1J7") (pintype "passive"))
      (node (ref "U1") (pin "1J9") (pinfunction "VSS_1J9") (pintype "passive"))
      (node (ref "U1") (pin "1K10") (pinfunction "VSS_1K10") (pintype "passive"))
      (node (ref "U1") (pin "1K12") (pinfunction "VSS_1K12") (pintype "passive"))
      (node (ref "U1") (pin "1K2") (pinfunction "VSS_1K2") (pintype "passive"))
      (node (ref "U1") (pin "1K4") (pinfunction "VSS_1K4") (pintype "passive"))
      (node (ref "U1") (pin "1K6") (pinfunction "VSS_1K6") (pintype "passive"))
      (node (ref "U1") (pin "1K8") (pinfunction "VSS_1K8") (pintype "passive"))
      (node (ref "U1") (pin "A1") (pinfunction "VSS_A1") (pintype "passive"))
      (node (ref "U1") (pin "A2") (pinfunction "VSS_A2") (pintype "passive"))
      (node (ref "U1") (pin "A27") (pinfunction "VSS_A27") (pintype "passive"))
      (node (ref "U1") (pin "AC11") (pinfunction "VSS_AC11") (pintype "passive"))
      (node (ref "U1") (pin "AC3") (pinfunction "VSSAON_AC3") (pintype "passive"))
      (node (ref "U1") (pin "AC5") (pinfunction "VSSA_AC5") (pintype "passive"))
      (node (ref "U1") (pin "AF6") (pinfunction "VREFN_AF6") (pintype "passive"))
      (node (ref "U1") (pin "AG1") (pinfunction "VSS_AG1") (pintype "passive"))
      (node (ref "U1") (pin "AG27") (pinfunction "VSS_AG27") (pintype "passive"))
      (node (ref "U1") (pin "C10") (pinfunction "VSS_C10") (pintype "passive"))
      (node (ref "U1") (pin "C6") (pinfunction "VSS_C6") (pintype "passive"))
      (node (ref "U1") (pin "E7") (pinfunction "VSS_E7") (pintype "passive"))
      (node (ref "U1") (pin "F12") (pinfunction "VSS_F12") (pintype "passive"))
      (node (ref "U1") (pin "F14") (pinfunction "VSS_F14") (pintype "passive"))
      (node (ref "U1") (pin "F16") (pinfunction "VSS_F16") (pintype "passive"))
      (node (ref "U1") (pin "F3") (pinfunction "VSS_F3") (pintype "passive"))
      (node (ref "U1") (pin "J7") (pinfunction "VSS_J7") (pintype "passive"))
      (node (ref "U1") (pin "K3") (pinfunction "VSS_K3") (pintype "passive"))
      (node (ref "U1") (pin "V6") (pinfunction "VSS_V6") (pintype "passive"))
      (node (ref "U1") (pin "Y4") (pinfunction "VSS_Y4") (pintype "passive"))
    )
    (net (code "3") (name "Net-(C14-Pad2)") (class "Default")
      (node (ref "C14") (pin "2") (pinfunction "2_2") (pintype "passive"))
      (node (ref "D6") (pin "2") (pinfunction "2_2") (pintype "passive"))
      (node (ref "R66") (pin "2") (pinfunction "2_2") (pintype "passive"))
    )
    (net (code "4") (name "Net-(CN12-Pad1)") (class "Default")
      (node (ref "CN12") (pin "1") (pinfunction "1_1") (pintype "passive"))
      (node (ref "R66") (pin "1") (pinfunction "1_1") (pintype "passive"))
    )
    (net (code "5") (name "Net-(D6-Pad1)") (class "Default")
      (node (ref "D6") (pin "1") (pinfunction "1_1") (pintype "passive"))
      (node (ref "R67") (pin "1") (pinfunction "1_1") (pintype "passive"))
    )
    (net (code "6") (name "Net-(U1G-V08CAP)") (class "Default")
      (node (ref "C225") (pin "2") (pinfunction "2_2") (pintype "passive"))
      (node (ref "U1") (pin "R7") (pinfunction "V08CAP_R7") (pintype "passive"))
    )
    (net (code "7") (name "Net-(U1G-VDD33UCPD)") (class "Default")
      (node (ref "C251") (pin "2") (pinfunction "2_2") (pintype "passive"))
      (node (ref "R286") (pin "2") (pinfunction "2_2") (pintype "passive"))
      (node (ref "U1") (pin "AE21") (pinfunction "VDD33USB_AE21") (pintype "passive"))
      (node (ref "U1") (pin "AE22") (pinfunction "VDD33UCPD_AE22") (pintype "passive"))
    )
    (net (code "8") (name "Net-(U1G-VDDA18ADC)") (class "Default")
      (node (ref "C235") (pin "2") (pinfunction "2_2") (pintype "passive"))
      (node (ref "C244") (pin "2") (pinfunction "2_2") (pintype "passive"))
      (node (ref "R267") (pin "1") (pinfunction "1_1") (pintype "passive"))
      (node (ref "U1") (pin "AB6") (pinfunction "VDDA18ADC_AB6") (pintype "passive"))
    )
    (net (code "9") (name "Net-(U1G-VDDCOMBOPHY)") (class "Default")
      (node (ref "C15") (pin "2") (pinfunction "2_2") (pintype "passive"))
      (node (ref "C252") (pin "2") (pinfunction "2_2") (pintype "passive"))
      (node (ref "C260") (pin "2") (pinfunction "2_2") (pintype "passive"))
      (node (ref "R11") (pin "2") (pinfunction "2_2") (pintype "passive"))
      (node (ref "U1") (pin "AB20") (pinfunction "VDDCOMBOPHY_AB20") (pintype "passive"))
      (node (ref "U1") (pin "AB22") (pinfunction "VDDCOMBOPHYTX_AB22") (pintype "passive"))
      (node (ref "U1") (pin "AC21") (pinfunction "VDDPCIECLK_AC21") (pintype "passive"))
    )
    (net (code "10") (name "VBAT") (class "Default")
      (node (ref "C87") (pin "2") (pinfunction "2_2") (pintype "passive"))
      (node (ref "D6") (pin "3") (pinfunction "3_3") (pintype "passive"))
      (node (ref "U1") (pin "T6") (pinfunction "VBAT_T6") (pintype "passive"))
    )
    (net (code "11") (name "VDD3V3_USB") (class "Default")
      (node (ref "R286") (pin "1") (pinfunction "1_1") (pintype "passive"))
    )
    (net (code "12") (name "VDDA1V8_AON") (class "Default")
      (node (ref "C234") (pin "2") (pinfunction "2_2") (pintype "passive"))
      (node (ref "U1") (pin "AB3") (pinfunction "VDDA18AON_AB3") (pintype "passive"))
    )
    (net (code "13") (name "VDDCORE") (class "Default")
      (node (ref "C16") (pin "2") (pinfunction "2_2") (pintype "passive"))
      (node (ref "C192") (pin "2") (pinfunction "2_2") (pintype "passive"))
      (node (ref "C201") (pin "2") (pinfunction "2_2") (pintype "passive"))
      (node (ref "C44") (pin "1") (pinfunction "1_1") (pintype "passive"))
      (node (ref "C45") (pin "2") (pinfunction "2_2") (pintype "passive"))
      (node (ref "C46") (pin "2") (pinfunction "2_2") (pintype "passive"))
      (node (ref "C47") (pin "1") (pinfunction "1_1") (pintype "passive"))
      (node (ref "C48") (pin "2") (pinfunction "2_2") (pintype "passive"))
      (node (ref "C49") (pin "2") (pinfunction "2_2") (pintype "passive"))
      (node (ref "C50") (pin "2") (pinfunction "2_2") (pintype "passive"))
      (node (ref "C51") (pin "2") (pinfunction "2_2") (pintype "passive"))
      (node (ref "R11") (pin "1") (pinfunction "1_1") (pintype "passive"))
      (node (ref "U1") (pin "1C1") (pinfunction "VDDCORE_1C1") (pintype "passive"))
      (node (ref "U1") (pin "1C3") (pinfunction "VDDCORE_1C3") (pintype "passive"))
      (node (ref "U1") (pin "1C5") (pinfunction "VDDCORE_1C5") (pintype "passive"))
      (node (ref "U1") (pin "1D2") (pinfunction "VDDCORE_1D2") (pintype "passive"))
      (node (ref "U1") (pin "1D4") (pinfunction "VDDCORE_1D4") (pintype "passive"))
      (node (ref "U1") (pin "1E3") (pinfunction "VDDCORE_1E3") (pintype "passive"))
      (node (ref "U1") (pin "1E5") (pinfunction "VDDCORE_1E5") (pintype "passive"))
      (node (ref "U1") (pin "1F2") (pinfunction "VDDCORE_1F2") (pintype "passive"))
      (node (ref "U1") (pin "1F4") (pinfunction "VDDCORE_1F4") (pintype "passive"))
      (node (ref "U1") (pin "E5") (pinfunction "VDDCSI_E5") (pintype "passive"))
      (node (ref "U1") (pin "F4") (pinfunction "VDDLVDS_F4") (pintype "passive"))
      (node (ref "U1") (pin "F8") (pinfunction "VDDDSI_F8") (pintype "passive"))
    )
    (net (code "14") (name "VDDCPU") (class "Default")
      (node (ref "C10") (pin "2") (pinfunction "2_2") (pintype "passive"))
      (node (ref "C11") (pin "2") (pinfunction "2_2") (pintype "passive"))
      (node (ref "C6") (pin "1") (pinfunction "1_1") (pintype "passive"))
      (node (ref "C64") (pin "2") (pinfunction "2_2") (pintype "passive"))
      (node (ref "C68") (pin "2") (pinfunction "2_2") (pintype "passive"))
      (node (ref "C69") (pin "2") (pinfunction "2_2") (pintype "passive"))
      (node (ref "C7") (pin "2") (pinfunction "2_2") (pintype "passive"))
      (node (ref "C8") (pin "1") (pinfunction "1_1") (pintype "passive"))
      (node (ref "U1") (pin "1C7") (pinfunction "VDDCPU_1C7") (pintype "passive"))
      (node (ref "U1") (pin "1C9") (pinfunction "VDDCPU_1C9") (pintype "passive"))
      (node (ref "U1") (pin "1D10") (pinfunction "VDDCPU_1D10") (pintype "passive"))
      (node (ref "U1") (pin "1D6") (pinfunction "VDDCPU_1D6") (pintype "passive"))
      (node (ref "U1") (pin "1D8") (pinfunction "VDDCPU_1D8") (pintype "passive"))
      (node (ref "U1") (pin "F18") (pinfunction "VDDCPU_F18") (pintype "passive"))
      (node (ref "U1") (pin "G15") (pinfunction "VDDCPU_G15") (pintype "passive"))
      (node (ref "U1") (pin "G17") (pinfunction "VDDCPU_G17") (pintype "passive"))
    )
    (net (code "15") (name "VDDGPU") (class "Default")
      (node (ref "C1") (pin "2") (pinfunction "2_2") (pintype "passive"))
      (node (ref "C2") (pin "2") (pinfunction "2_2") (pintype "passive"))
      (node (ref "C3") (pin "2") (pinfunction "2_2") (pintype "passive"))
      (node (ref "C4") (pin "2") (pinfunction "2_2") (pintype "passive"))
      (node (ref "C5") (pin "2") (pinfunction "2_2") (pintype "passive"))
      (node (ref "C52") (pin "2") (pinfunction "2_2") (pintype "passive"))
      (node (ref "C58") (pin "2") (pinfunction "2_2") (pintype "passive"))
      (node (ref "C59") (pin "2") (pinfunction "2_2") (pintype "passive"))
      (node (ref "U1") (pin "1G7") (pinfunction "VDDGPU_1G7") (pintype "passive"))
      (node (ref "U1") (pin "1G9") (pinfunction "VDDGPU_1G9") (pintype "passive"))
      (node (ref "U1") (pin "1H10") (pinfunction "VDDGPU_1H10") (pintype "passive"))
      (node (ref "U1") (pin "1H6") (pinfunction "VDDGPU_1H6") (pintype "passive"))
      (node (ref "U1") (pin "1H8") (pinfunction "VDDGPU_1H8") (pintype "passive"))
      (node (ref "U1") (pin "1L7") (pinfunction "VDDGPU_1L7") (pintype "passive"))
      (node (ref "U1") (pin "1L9") (pinfunction "VDDGPU_1L9") (pintype "passive"))
      (node (ref "U1") (pin "1M10") (pinfunction "VDDGPU_1M10") (pintype "passive"))
      (node (ref "U1") (pin "1M6") (pinfunction "VDDGPU_1M6") (pintype "passive"))
      (node (ref "U1") (pin "1M8") (pinfunction "VDDGPU_1M8") (pintype "passive"))
    )
    (net (code "16") (name "VDDIO") (class "Default")
      (node (ref "C12") (pin "1") (pinfunction "1_1") (pintype "passive"))
      (node (ref "C17") (pin "2") (pinfunction "2_2") (pintype "passive"))
      (node (ref "C196") (pin "2") (pinfunction "2_2") (pintype "passive"))
      (node (ref "C70") (pin "1") (pinfunction "1_1") (pintype "passive"))
      (node (ref "C71") (pin "2") (pinfunction "2_2") (pintype "passive"))
      (node (ref "C72") (pin "2") (pinfunction "2_2") (pintype "passive"))
      (node (ref "C74") (pin "2") (pinfunction "2_2") (pintype "passive"))
      (node (ref "R67") (pin "2") (pinfunction "2_2") (pintype "passive"))
      (node (ref "U1") (pin "1L1") (pinfunction "VDD_1L1") (pintype "passive"))
      (node (ref "U1") (pin "1L3") (pinfunction "VDD_1L3") (pintype "passive"))
      (node (ref "U1") (pin "1L5") (pinfunction "VDD_1L5") (pintype "passive"))
      (node (ref "U1") (pin "1M2") (pinfunction "VDD_1M2") (pintype "passive"))
      (node (ref "U1") (pin "1M4") (pinfunction "VDD_1M4") (pintype "passive"))
      (node (ref "U1") (pin "D10") (pinfunction "VDDIO3_D10") (pintype "passive"))
      (node (ref "U1") (pin "E11") (pinfunction "VDDIO3_E11") (pintype "passive"))
      (node (ref "U1") (pin "E9") (pinfunction "VDDIO4_E9") (pintype "passive"))
      (node (ref "U1") (pin "G11") (pinfunction "VDDIO4_G11") (pintype "passive"))
    )
    (net (code "17") (name "VDDIO_SDCARD") (class "Default")
      (node (ref "C195") (pin "2") (pinfunction "2_2") (pintype "passive"))
      (node (ref "U1") (pin "D14") (pinfunction "VDDIO1_D14") (pintype "passive"))
      (node (ref "U1") (pin "E13") (pinfunction "VDDIO1_E13") (pintype "passive"))
    )
    (net (code "18") (name "VDD_DDR") (class "Default")
      (node (ref "C13") (pin "2") (pinfunction "2_2") (pintype "passive"))
      (node (ref "C75") (pin "2") (pinfunction "2_2") (pintype "passive"))
      (node (ref "C76") (pin "2") (pinfunction "2_2") (pintype "passive"))
      (node (ref "C77") (pin "1") (pinfunction "1_1") (pintype "passive"))
      (node (ref "C82") (pin "2") (pinfunction "2_2") (pintype "passive"))
      (node (ref "U1") (pin "1C11") (pinfunction "VDDQDDR_1C11") (pintype "passive"))
      (node (ref "U1") (pin "1D12") (pinfunction "VDDQDDR_1D12") (pintype "passive"))
      (node (ref "U1") (pin "1E11") (pinfunction "VDDQDDR_1E11") (pintype "passive"))
      (node (ref "U1") (pin "1F12") (pinfunction "VDDQDDR_1F12") (pintype "passive"))
      (node (ref "U1") (pin "1L11") (pinfunction "VDDQDDR_1L11") (pintype "passive"))
      (node (ref "U1") (pin "1M12") (pinfunction "VDDQDDR_1M12") (pintype "passive"))
      (node (ref "U1") (pin "M22") (pinfunction "VDDQDDR_M22") (pintype "passive"))
      (node (ref "U1") (pin "N21") (pinfunction "VDDQDDR_N21") (pintype "passive"))
      (node (ref "U1") (pin "R21") (pinfunction "VDDQDDR_R21") (pintype "passive"))
    )
    (net (code "19") (name "VREF+") (class "Default")
      (node (ref "C248") (pin "2") (pinfunction "2_2") (pintype "passive"))
      (node (ref "C250") (pin "2") (pinfunction "2_2") (pintype "passive"))
      (node (ref "R269") (pin "2") (pinfunction "2_2") (pintype "passive"))
      (node (ref "U1") (pin "AG6") (pinfunction "VREFP_AG6") (pintype "passive"))
    )
  )
)
